# IO.net
KiCad netlist of a schematic drawn in Altium Designer
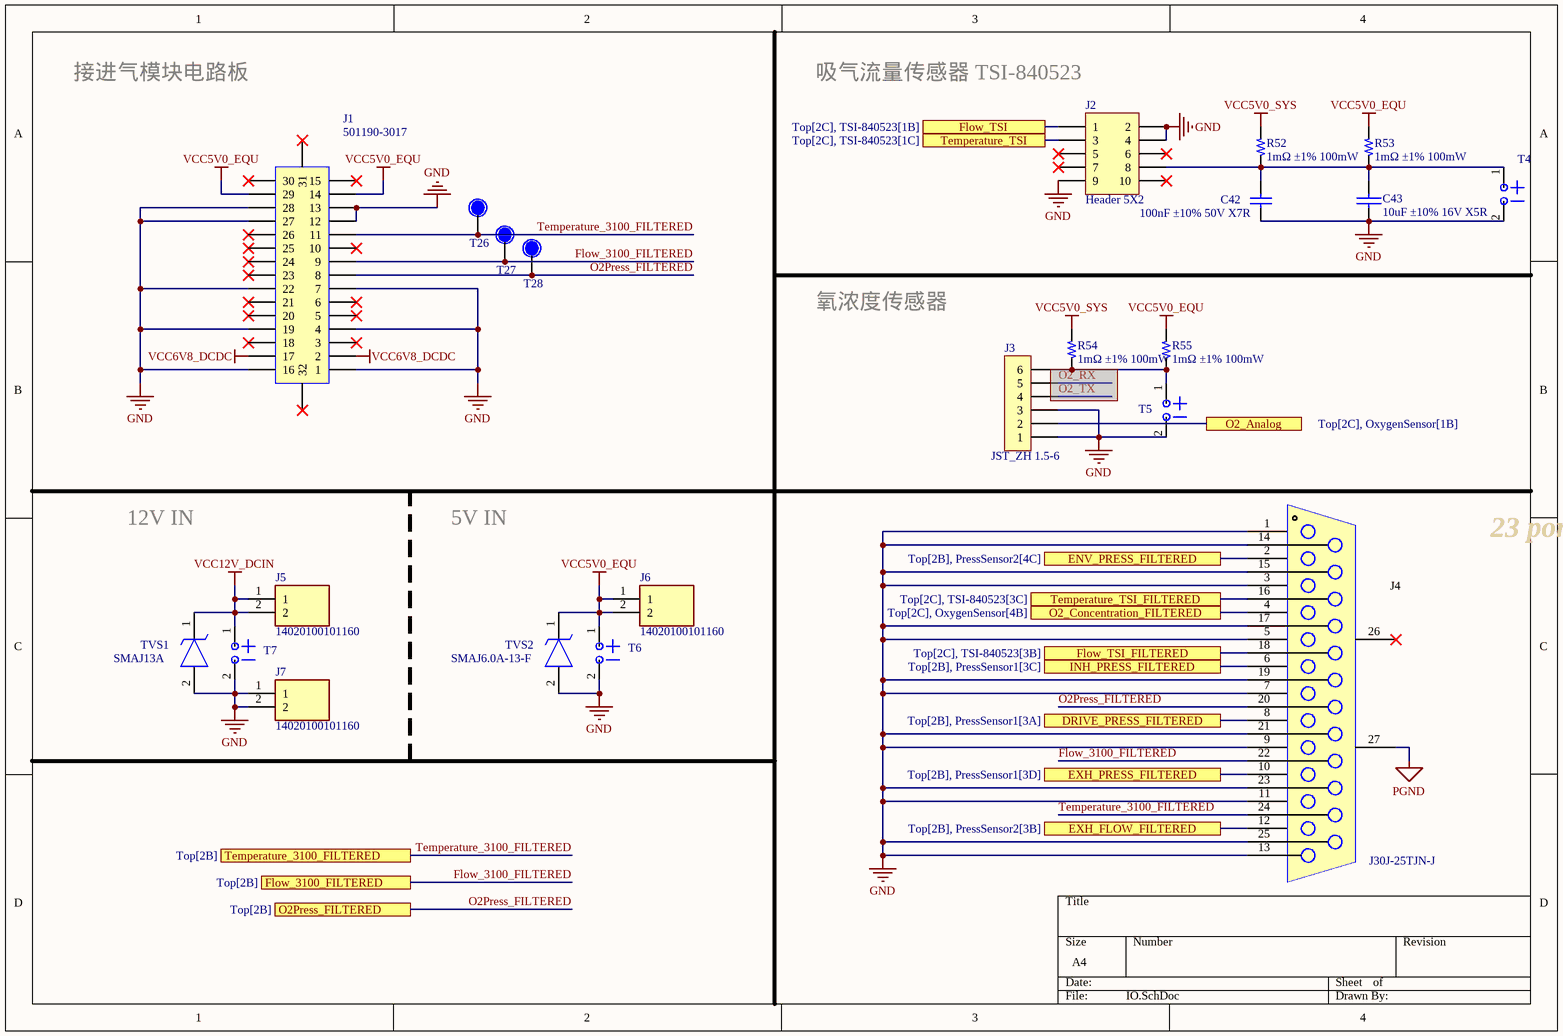
[diagram p0: IO.SchDoc]

(export (version "E")
  (design (tool "Eeschema 10.0.6"))
  (components
    (comp (ref "C42")
      (value "100nF ±10% 50V X7R")
      (footprint "C-0603")
      (libsource (lib "电容") (part "100nF_1"))
    )
    (comp (ref "C43")
      (value "10uF ±10% 16V X5R")
      (footprint "C-0805")
      (description "Capacitor")
      (libsource (lib "*") (part "CAP"))
    )
    (comp (ref "J1")
      (value "501190-3017")
      (footprint "501190-3017")
      (libsource (lib "常用") (part "501190-3017"))
    )
    (comp (ref "J2")
      (value "Header 5X2")
      (footprint "878311041")
      (description "Header, 5-Pin, Dual row")
      (fields (field (name "PUBLISHER") "Altium Limited"))
      (libsource (lib "Miscellaneous Connectors") (part "Header 5X2"))
    )
    (comp (ref "J3")
      (value "JST_ZH 1.5-6")
      (footprint "JST_ZH 1.5-6")
      (description "品牌：JST 型号：B6B-ZR，直插，间距1.5，6pin")
      (libsource (lib "connectors") (part "JST_ZH 1.5-6"))
    )
    (comp (ref "J4")
      (value "J30J-25TJN-J")
      (footprint "J30J-25TJN-J")
      (fields
        (field (name "MANUFACTURER") "BOOMELE(博穆精密)")
        (field (name "MANUFACTURER PART") "GH1.25-5PLTPZ")
      )
      (libsource (lib "Connectivity_Plugs") (part "J30J-25TJN-J"))
    )
    (comp (ref "J5")
      (value "14020100101160")
      (footprint "SamacSys:14020100101160")
      (description "Connector")
      (libsource (lib "*") (part "14020100101160"))
    )
    (comp (ref "J6")
      (value "14020100101160")
      (footprint "SamacSys:14020100101160")
      (description "Connector")
      (libsource (lib "*") (part "14020100101160"))
    )
    (comp (ref "J7")
      (value "14020100101160")
      (footprint "SamacSys:14020100101160")
      (description "Connector")
      (libsource (lib "*") (part "14020100101160"))
    )
    (comp (ref "R52")
      (value "1mΩ ±1% 100mW")
      (footprint "R-0603")
      (description "国巨\r\n1mΩ ±1% 100mW")
      (libsource (lib "电阻") (part "10K_1"))
    )
    (comp (ref "R53")
      (value "1mΩ ±1% 100mW")
      (footprint "R-0603")
      (description "国巨\r\n1mΩ ±1% 100mW")
      (libsource (lib "电阻") (part "10K_1"))
    )
    (comp (ref "R54")
      (value "1mΩ ±1% 100mW")
      (footprint "R-0603")
      (description "国巨\r\n1mΩ ±1% 100mW")
      (libsource (lib "电阻") (part "10K_1"))
    )
    (comp (ref "R55")
      (value "1mΩ ±1% 100mW")
      (footprint "R-0603")
      (description "国巨\r\n1mΩ ±1% 100mW")
      (libsource (lib "电阻") (part "10K_1"))
    )
    (comp (ref "T4") (value "POWER_TEST") (footprint "BT") (libsource (lib "其它") (part "POWER_TEST")))
    (comp (ref "T5") (value "POWER_TEST") (footprint "BT") (libsource (lib "其它") (part "POWER_TEST")))
    (comp (ref "T6") (value "POWER_TEST") (footprint "BT") (libsource (lib "其它") (part "POWER_TEST")))
    (comp (ref "T7") (value "POWER_TEST") (footprint "BT") (libsource (lib "其它") (part "POWER_TEST")))
    (comp (ref "T26")
      (value "Test?")
      (footprint "TestPad_SMD")
      (description "TestPad_SMD")
      (libsource (lib "Component") (part "TestPad_SMD"))
    )
    (comp (ref "T27")
      (value "Test?")
      (footprint "TestPad_SMD")
      (description "TestPad_SMD")
      (libsource (lib "Component") (part "TestPad_SMD"))
    )
    (comp (ref "T28")
      (value "Test?")
      (footprint "TestPad_SMD")
      (description "TestPad_SMD")
      (libsource (lib "Component") (part "TestPad_SMD"))
    )
    (comp (ref "TVS1")
      (value "SMAJ13A")
      (footprint "SamacSys:DIONM5126X250N")
      (description "TVS Diode (Uni-directional)")
      (fields (field (name "MOUSER PART NUMBER") "576-SMAJ13A"))
      (libsource (lib "*") (part "SMAJ13A"))
    )
    (comp (ref "TVS2")
      (value "SMAJ6.0A-13-F")
      (footprint "SamacSys:DIOM5226X240N")
      (description "TVS Diode (Uni-directional)")
      (fields (field (name "MOUSER PART NUMBER") "621-SMAJ6.0A-13-F"))
      (libsource (lib "*") (part "SMAJ6.0A-13-F"))
    )
  )
  (nets
    (net (code "1") (name "/DRIVE_PRESS_FILTERED") (class "Default")
      (node (ref "J4") (pin "8") (pinfunction "8_8") (pintype "passive"))
    )
    (net (code "2") (name "/ENV_PRESS_FILTERED") (class "Default")
      (node (ref "J4") (pin "2") (pinfunction "2_2") (pintype "passive"))
    )
    (net (code "3") (name "/EXH_FLOW_FILTERED") (class "Default")
      (node (ref "J4") (pin "12") (pinfunction "12_12") (pintype "passive"))
    )
    (net (code "4") (name "/EXH_PRESS_FILTERED") (class "Default")
      (node (ref "J4") (pin "10") (pinfunction "10_10") (pintype "passive"))
    )
    (net (code "5") (name "/Flow_3100_FILTERED") (class "Default")
      (node (ref "J1") (pin "9") (pinfunction "9_9") (pintype "passive"))
      (node (ref "J4") (pin "22") (pinfunction "22_22") (pintype "passive"))
      (node (ref "T27") (pin "1") (pinfunction "1_1") (pintype "passive"))
    )
    (net (code "6") (name "/Flow_TSI") (class "Default")
      (node (ref "J2") (pin "1") (pinfunction "1_1") (pintype "passive"))
    )
    (net (code "7") (name "/Flow_TSI_FILTERED") (class "Default")
      (node (ref "J4") (pin "18") (pinfunction "18_18") (pintype "passive"))
    )
    (net (code "8") (name "/INH_PRESS_FILTERED") (class "Default")
      (node (ref "J4") (pin "6") (pinfunction "6_6") (pintype "passive"))
    )
    (net (code "9") (name "/O2Press_FILTERED") (class "Default")
      (node (ref "J1") (pin "8") (pinfunction "8_8") (pintype "passive"))
      (node (ref "J4") (pin "20") (pinfunction "20_20") (pintype "passive"))
      (node (ref "T28") (pin "1") (pinfunction "1_1") (pintype "passive"))
    )
    (net (code "10") (name "/O2_Analog") (class "Default")
      (node (ref "J3") (pin "2") (pinfunction "2_2") (pintype "passive"))
    )
    (net (code "11") (name "/O2_Concentration_FILTERED") (class "Default")
      (node (ref "J4") (pin "4") (pinfunction "4_4") (pintype "passive"))
    )
    (net (code "12") (name "/O2_RX") (class "Default")
      (node (ref "J3") (pin "5") (pinfunction "5_5") (pintype "passive"))
    )
    (net (code "13") (name "/O2_TX") (class "Default")
      (node (ref "J3") (pin "4") (pinfunction "4_4") (pintype "passive"))
    )
    (net (code "14") (name "/Temperature_3100_FILTERED") (class "Default")
      (node (ref "J1") (pin "11") (pinfunction "11_11") (pintype "passive"))
      (node (ref "J4") (pin "24") (pinfunction "24_24") (pintype "passive"))
      (node (ref "T26") (pin "1") (pinfunction "1_1") (pintype "passive"))
    )
    (net (code "15") (name "/Temperature_TSI") (class "Default")
      (node (ref "J2") (pin "3") (pinfunction "3_3") (pintype "passive"))
    )
    (net (code "16") (name "/Temperature_TSI_FILTERED") (class "Default")
      (node (ref "J4") (pin "16") (pinfunction "16_16") (pintype "passive"))
    )
    (net (code "17") (name "GND") (class "Default")
      (node (ref "C42") (pin "1") (pinfunction "1_1") (pintype "passive"))
      (node (ref "C43") (pin "1") (pinfunction "1_1") (pintype "passive"))
      (node (ref "J1") (pin "1") (pinfunction "1_1") (pintype "passive"))
      (node (ref "J1") (pin "12") (pinfunction "12_12") (pintype "passive"))
      (node (ref "J1") (pin "13") (pinfunction "13_13") (pintype "passive"))
      (node (ref "J1") (pin "16") (pinfunction "16_16") (pintype "passive"))
      (node (ref "J1") (pin "19") (pinfunction "19_19") (pintype "passive"))
      (node (ref "J1") (pin "22") (pinfunction "22_22") (pintype "passive"))
      (node (ref "J1") (pin "27") (pinfunction "27_27") (pintype "passive"))
      (node (ref "J1") (pin "28") (pinfunction "28_28") (pintype "passive"))
      (node (ref "J1") (pin "4") (pinfunction "4_4") (pintype "passive"))
      (node (ref "J1") (pin "7") (pinfunction "7_7") (pintype "passive"))
      (node (ref "J2") (pin "2") (pinfunction "2_2") (pintype "passive"))
      (node (ref "J2") (pin "4") (pinfunction "4_4") (pintype "passive"))
      (node (ref "J2") (pin "9") (pinfunction "9_9") (pintype "passive"))
      (node (ref "J3") (pin "1") (pinfunction "1_1") (pintype "passive"))
      (node (ref "J3") (pin "3") (pinfunction "3_3") (pintype "passive"))
      (node (ref "J4") (pin "1") (pinfunction "1_1") (pintype "passive"))
      (node (ref "J4") (pin "11") (pinfunction "11_11") (pintype "passive"))
      (node (ref "J4") (pin "13") (pinfunction "13_13") (pintype "passive"))
      (node (ref "J4") (pin "14") (pinfunction "14_14") (pintype "passive"))
      (node (ref "J4") (pin "15") (pinfunction "15_15") (pintype "passive"))
      (node (ref "J4") (pin "17") (pinfunction "17_17") (pintype "passive"))
      (node (ref "J4") (pin "19") (pinfunction "19_19") (pintype "passive"))
      (node (ref "J4") (pin "21") (pinfunction "21_21") (pintype "passive"))
      (node (ref "J4") (pin "23") (pinfunction "23_23") (pintype "passive"))
      (node (ref "J4") (pin "25") (pinfunction "25_25") (pintype "passive"))
      (node (ref "J4") (pin "3") (pinfunction "3_3") (pintype "passive"))
      (node (ref "J4") (pin "5") (pinfunction "5_5") (pintype "passive"))
      (node (ref "J4") (pin "7") (pinfunction "7_7") (pintype "passive"))
      (node (ref "J4") (pin "9") (pinfunction "9_9") (pintype "passive"))
      (node (ref "J7") (pin "1") (pinfunction "1_1") (pintype "passive"))
      (node (ref "J7") (pin "2") (pinfunction "2_2") (pintype "passive"))
      (node (ref "T4") (pin "2") (pinfunction "-_2") (pintype "passive"))
      (node (ref "T5") (pin "2") (pinfunction "-_2") (pintype "passive"))
      (node (ref "T6") (pin "2") (pinfunction "-_2") (pintype "passive"))
      (node (ref "T7") (pin "2") (pinfunction "-_2") (pintype "passive"))
      (node (ref "TVS1") (pin "2") (pinfunction "A_2") (pintype "passive"))
      (node (ref "TVS2") (pin "2") (pinfunction "A_2") (pintype "passive"))
    )
    (net (code "18") (name "Net-(R52-TOP)") (class "Default")
      (node (ref "C42") (pin "2") (pinfunction "2_2") (pintype "passive"))
      (node (ref "C43") (pin "2") (pinfunction "2_2") (pintype "passive"))
      (node (ref "J2") (pin "8") (pinfunction "8_8") (pintype "passive"))
      (node (ref "R52") (pin "1") (pinfunction "TOP_1") (pintype "passive"))
      (node (ref "R53") (pin "1") (pinfunction "TOP_1") (pintype "passive"))
      (node (ref "T4") (pin "1") (pinfunction "+_1") (pintype "passive"))
    )
    (net (code "19") (name "Net-(R54-TOP)") (class "Default")
      (node (ref "J3") (pin "6") (pinfunction "6_6") (pintype "passive"))
      (node (ref "R54") (pin "1") (pinfunction "TOP_1") (pintype "passive"))
      (node (ref "R55") (pin "1") (pinfunction "TOP_1") (pintype "passive"))
      (node (ref "T5") (pin "1") (pinfunction "+_1") (pintype "passive"))
    )
    (net (code "20") (name "PGND") (class "Default")
      (node (ref "J4") (pin "27") (pinfunction "27_27") (pintype "passive"))
    )
    (net (code "21") (name "VCC5V0_EQU") (class "Default")
      (node (ref "J1") (pin "14") (pinfunction "14_14") (pintype "passive"))
      (node (ref "J1") (pin "29") (pinfunction "29_29") (pintype "passive"))
      (node (ref "J6") (pin "1") (pinfunction "1_1") (pintype "passive"))
      (node (ref "J6") (pin "2") (pinfunction "2_2") (pintype "passive"))
      (node (ref "R53") (pin "2") (pinfunction "BOT_2") (pintype "passive"))
      (node (ref "R55") (pin "2") (pinfunction "BOT_2") (pintype "passive"))
      (node (ref "T6") (pin "1") (pinfunction "+_1") (pintype "passive"))
      (node (ref "TVS2") (pin "1") (pinfunction "K_1") (pintype "passive"))
    )
    (net (code "22") (name "VCC5V0_SYS") (class "Default")
      (node (ref "R52") (pin "2") (pinfunction "BOT_2") (pintype "passive"))
      (node (ref "R54") (pin "2") (pinfunction "BOT_2") (pintype "passive"))
    )
    (net (code "23") (name "VCC6V8_DCDC") (class "Default")
      (node (ref "J1") (pin "17") (pinfunction "17_17") (pintype "passive"))
      (node (ref "J1") (pin "2") (pinfunction "2_2") (pintype "passive"))
    )
    (net (code "24") (name "VCC12V_DCIN") (class "Default")
      (node (ref "J5") (pin "1") (pinfunction "1_1") (pintype "passive"))
      (node (ref "J5") (pin "2") (pinfunction "2_2") (pintype "passive"))
      (node (ref "T7") (pin "1") (pinfunction "+_1") (pintype "passive"))
      (node (ref "TVS1") (pin "1") (pinfunction "K_1") (pintype "passive"))
    )
    (net (code "25") (name "unconnected-(J1-Pad3)") (class "Default")
      (node (ref "J1") (pin "3") (pinfunction "3_3") (pintype "passive+no_connect"))
    )
    (net (code "26") (name "unconnected-(J1-Pad5)") (class "Default")
      (node (ref "J1") (pin "5") (pinfunction "5_5") (pintype "passive+no_connect"))
    )
    (net (code "27") (name "unconnected-(J1-Pad6)") (class "Default")
      (node (ref "J1") (pin "6") (pinfunction "6_6") (pintype "passive+no_connect"))
    )
    (net (code "28") (name "unconnected-(J1-Pad10)") (class "Default")
      (node (ref "J1") (pin "10") (pinfunction "10_10") (pintype "passive+no_connect"))
    )
    (net (code "29") (name "unconnected-(J1-Pad15)") (class "Default")
      (node (ref "J1") (pin "15") (pinfunction "15_15") (pintype "passive+no_connect"))
    )
    (net (code "30") (name "unconnected-(J1-Pad18)") (class "Default")
      (node (ref "J1") (pin "18") (pinfunction "18_18") (pintype "passive+no_connect"))
    )
    (net (code "31") (name "unconnected-(J1-Pad20)") (class "Default")
      (node (ref "J1") (pin "20") (pinfunction "20_20") (pintype "passive+no_connect"))
    )
    (net (code "32") (name "unconnected-(J1-Pad21)") (class "Default")
      (node (ref "J1") (pin "21") (pinfunction "21_21") (pintype "passive+no_connect"))
    )
    (net (code "33") (name "unconnected-(J1-Pad23)") (class "Default")
      (node (ref "J1") (pin "23") (pinfunction "23_23") (pintype "passive+no_connect"))
    )
    (net (code "34") (name "unconnected-(J1-Pad24)") (class "Default")
      (node (ref "J1") (pin "24") (pinfunction "24_24") (pintype "passive+no_connect"))
    )
    (net (code "35") (name "unconnected-(J1-Pad25)") (class "Default")
      (node (ref "J1") (pin "25") (pinfunction "25_25") (pintype "passive+no_connect"))
    )
    (net (code "36") (name "unconnected-(J1-Pad26)") (class "Default")
      (node (ref "J1") (pin "26") (pinfunction "26_26") (pintype "passive+no_connect"))
    )
    (net (code "37") (name "unconnected-(J1-Pad30)") (class "Default")
      (node (ref "J1") (pin "30") (pinfunction "30_30") (pintype "passive+no_connect"))
    )
    (net (code "38") (name "unconnected-(J1-Pad31)") (class "Default")
      (node (ref "J1") (pin "31") (pinfunction "31_31") (pintype "passive+no_connect"))
    )
    (net (code "39") (name "unconnected-(J1-Pad32)") (class "Default")
      (node (ref "J1") (pin "32") (pinfunction "32_32") (pintype "passive+no_connect"))
    )
    (net (code "40") (name "unconnected-(J2-Pad5)") (class "Default")
      (node (ref "J2") (pin "5") (pinfunction "5_5") (pintype "passive+no_connect"))
    )
    (net (code "41") (name "unconnected-(J2-Pad6)") (class "Default")
      (node (ref "J2") (pin "6") (pinfunction "6_6") (pintype "passive+no_connect"))
    )
    (net (code "42") (name "unconnected-(J2-Pad7)") (class "Default")
      (node (ref "J2") (pin "7") (pinfunction "7_7") (pintype "passive+no_connect"))
    )
    (net (code "43") (name "unconnected-(J2-Pad10)") (class "Default")
      (node (ref "J2") (pin "10") (pinfunction "10_10") (pintype "passive+no_connect"))
    )
    (net (code "44") (name "unconnected-(J4-Pad26)") (class "Default")
      (node (ref "J4") (pin "26") (pinfunction "26_26") (pintype "passive+no_connect"))
    )
  )
)
